# Keypad.net
KiCad netlist of a schematic drawn in Altium Designer
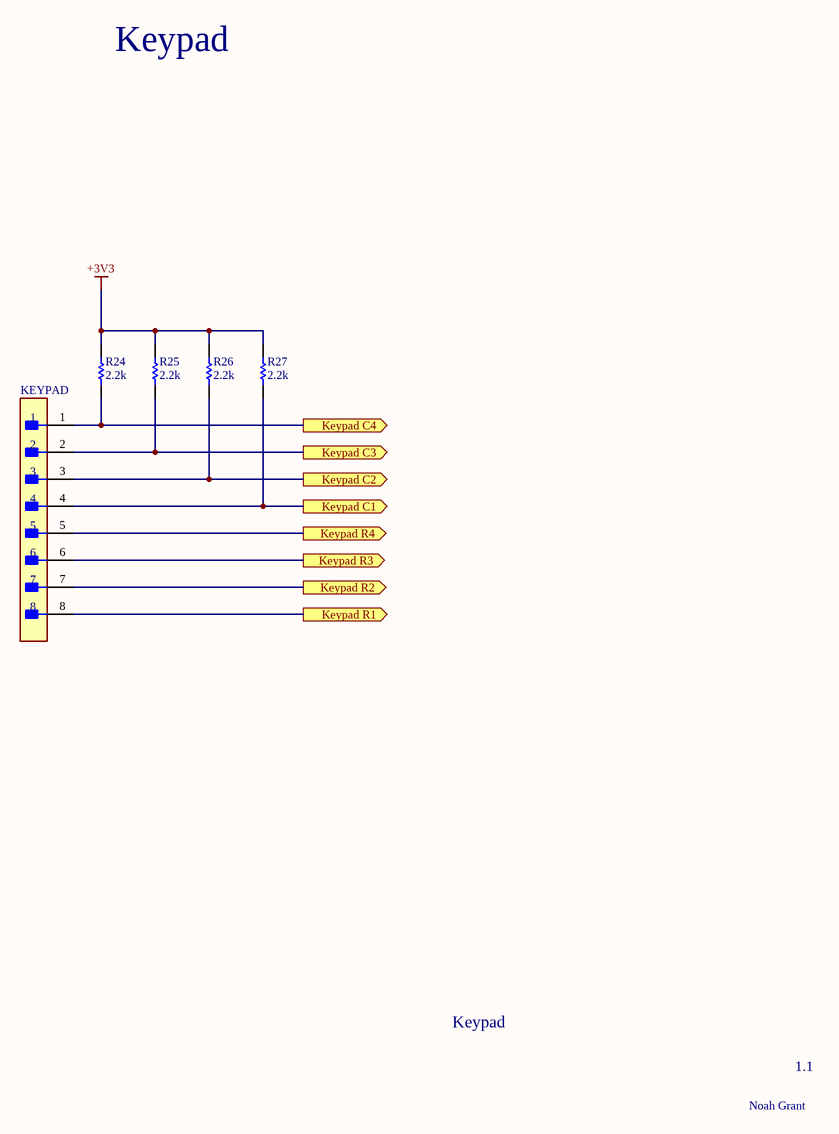
[diagram p0: Keypad.SchDoc]

(export (version "E")
  (design (tool "Eeschema 10.0.6"))
  (components
    (comp (ref "KEYPAD")
      (value "TSW-108-08-G-S")
      (footprint "FP-TSW-108-08-G-S-MFG")
      (description "CONN HEADER VERT 8POS 2.54MM")
      (fields
        (field (name "MANUFACTURER") "Samtec")
        (field (name "OCTOPART") "https://octopart.com/tsw-108-08-g-s-samtec-272653")
      )
      (libsource (lib "Altium Content Vault") (part "99ec2b232beb5d2356d4d77f6a047f0"))
    )
    (comp (ref "R24")
      (value "2.2k")
      (footprint "RESC1609X50X30NL10T20")
      (description "0603")
      (fields (field (name "PART NUMBER") "CRCW06032K20FKEA") (field (name "MANUFACTURER") "Vishay Dale"))
      (libsource (lib "Altium Content Vault") (part "RES"))
    )
    (comp (ref "R25")
      (value "2.2k")
      (footprint "RESC1609X50X30NL10T20")
      (description "0603")
      (fields (field (name "PART NUMBER") "CRCW06032K20FKEA") (field (name "MANUFACTURER") "Vishay Dale"))
      (libsource (lib "Altium Content Vault") (part "RES"))
    )
    (comp (ref "R26")
      (value "2.2k")
      (footprint "RESC1609X50X30NL10T20")
      (description "0603")
      (fields (field (name "PART NUMBER") "CRCW06032K20FKEA") (field (name "MANUFACTURER") "Vishay Dale"))
      (libsource (lib "Altium Content Vault") (part "RES"))
    )
    (comp (ref "R27")
      (value "2.2k")
      (footprint "RESC1609X50X30NL10T20")
      (description "0603")
      (fields (field (name "PART NUMBER") "CRCW06032K20FKEA") (field (name "MANUFACTURER") "Vishay Dale"))
      (libsource (lib "Altium Content Vault") (part "RES"))
    )
  )
  (nets
    (net (code "1") (name "+3V3") (class "Default")
      (node (ref "R24") (pin "2") (pinfunction "2_2") (pintype "passive"))
      (node (ref "R25") (pin "2") (pinfunction "2_2") (pintype "passive"))
      (node (ref "R26") (pin "2") (pinfunction "2_2") (pintype "passive"))
      (node (ref "R27") (pin "2") (pinfunction "2_2") (pintype "passive"))
    )
    (net (code "2") (name "/Keypad C1") (class "Default")
      (node (ref "KEYPAD") (pin "4") (pinfunction "4_4") (pintype "passive"))
      (node (ref "R27") (pin "1") (pinfunction "1_1") (pintype "passive"))
    )
    (net (code "3") (name "/Keypad C2") (class "Default")
      (node (ref "KEYPAD") (pin "3") (pinfunction "3_3") (pintype "passive"))
      (node (ref "R26") (pin "1") (pinfunction "1_1") (pintype "passive"))
    )
    (net (code "4") (name "/Keypad C3") (class "Default")
      (node (ref "KEYPAD") (pin "2") (pinfunction "2_2") (pintype "passive"))
      (node (ref "R25") (pin "1") (pinfunction "1_1") (pintype "passive"))
    )
    (net (code "5") (name "/Keypad C4") (class "Default")
      (node (ref "KEYPAD") (pin "1") (pinfunction "1_1") (pintype "passive"))
      (node (ref "R24") (pin "1") (pinfunction "1_1") (pintype "passive"))
    )
    (net (code "6") (name "/Keypad R1") (class "Default")
      (node (ref "KEYPAD") (pin "8") (pinfunction "8_8") (pintype "passive"))
    )
    (net (code "7") (name "/Keypad R2") (class "Default")
      (node (ref "KEYPAD") (pin "7") (pinfunction "7_7") (pintype "passive"))
    )
    (net (code "8") (name "/Keypad R3") (class "Default")
      (node (ref "KEYPAD") (pin "6") (pinfunction "6_6") (pintype "passive"))
    )
    (net (code "9") (name "/Keypad R4") (class "Default")
      (node (ref "KEYPAD") (pin "5") (pinfunction "5_5") (pintype "passive"))
    )
  )
)
